# music-lights.net
KiCad netlist of a schematic drawn in EAGLE
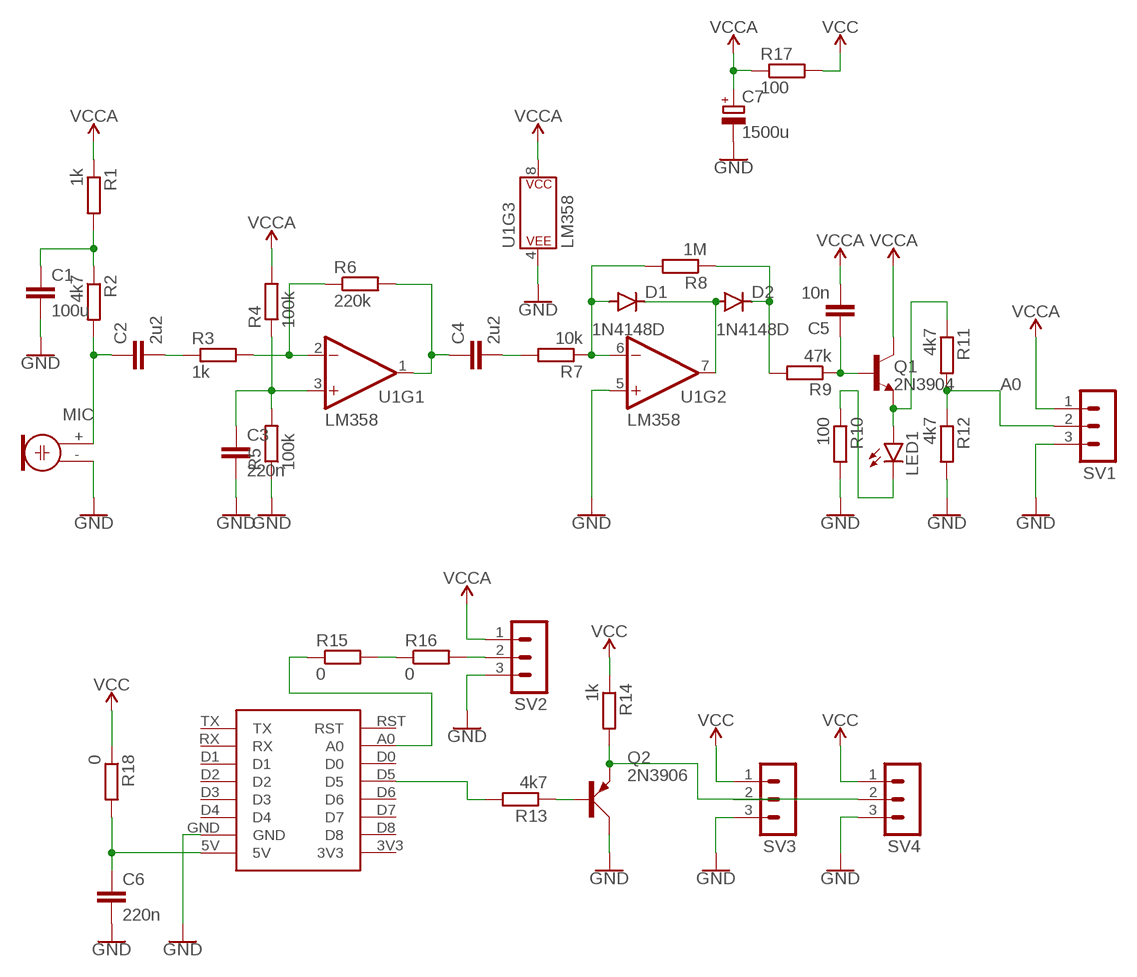
[diagram p0: schematic, sheet 1]

(export (version "E")
  (design (tool "Eeschema 10.0.6"))
  (components
    (comp (ref "C1")
      (value "100u")
      (footprint "eagle-import:C050-024X044")
      (libsource (lib "eagle-import") (part "C-EU050-024X044"))
    )
    (comp (ref "C2")
      (value "2u2")
      (footprint "eagle-import:C050-024X044")
      (libsource (lib "eagle-import") (part "C-EU050-024X044"))
    )
    (comp (ref "C3")
      (value "220n")
      (footprint "eagle-import:C050-024X044")
      (libsource (lib "eagle-import") (part "C-EU050-024X044"))
    )
    (comp (ref "C4")
      (value "2u2")
      (footprint "eagle-import:C050-024X044")
      (libsource (lib "eagle-import") (part "C-EU050-024X044"))
    )
    (comp (ref "C5")
      (value "10n")
      (footprint "eagle-import:C050-024X044")
      (libsource (lib "eagle-import") (part "C-EU050-024X044"))
    )
    (comp (ref "C6")
      (value "220n")
      (footprint "eagle-import:C050-024X044")
      (libsource (lib "eagle-import") (part "C-EU050-024X044"))
    )
    (comp (ref "C7")
      (value "1500u")
      (footprint "eagle-import:TT5D7L")
      (libsource (lib "eagle-import") (part "CPOL-EUTT5D7L"))
    )
    (comp (ref "D1")
      (value "1N4148D")
      (footprint "eagle-import:DO35-7")
      (libsource (lib "eagle-import") (part "1N4148DO35-7"))
    )
    (comp (ref "D2")
      (value "1N4148D")
      (footprint "eagle-import:DO35-7")
      (libsource (lib "eagle-import") (part "1N4148DO35-7"))
    )
    (comp (ref "LED1")
      (value "LED5MM")
      (footprint "eagle-import:LED5MM")
      (libsource (lib "eagle-import") (part "LED5MM"))
    )
    (comp (ref "MIC")
      (value "ELECTRET")
      (footprint "eagle-import:9.7ELECTRET")
      (libsource (lib "eagle-import") (part "ELECTRET"))
    )
    (comp (ref "Q1")
      (value "2N3904")
      (footprint "eagle-import:TO92")
      (libsource (lib "eagle-import") (part "2N3904"))
    )
    (comp (ref "Q2")
      (value "2N3906")
      (footprint "eagle-import:TO92D")
      (libsource (lib "eagle-import") (part "2N3906"))
    )
    (comp (ref "R1")
      (value "1k")
      (footprint "eagle-import:0207_7")
      (libsource (lib "eagle-import") (part "R-EU_0207/7"))
    )
    (comp (ref "R2")
      (value "4k7")
      (footprint "eagle-import:0207_7")
      (libsource (lib "eagle-import") (part "R-EU_0207/7"))
    )
    (comp (ref "R3")
      (value "1k")
      (footprint "eagle-import:0207_7")
      (libsource (lib "eagle-import") (part "R-EU_0207/7"))
    )
    (comp (ref "R4")
      (value "100k")
      (footprint "eagle-import:0207_7")
      (libsource (lib "eagle-import") (part "R-EU_0207/7"))
    )
    (comp (ref "R5")
      (value "100k")
      (footprint "eagle-import:0207_7")
      (libsource (lib "eagle-import") (part "R-EU_0207/7"))
    )
    (comp (ref "R6")
      (value "220k")
      (footprint "eagle-import:0207_7")
      (libsource (lib "eagle-import") (part "R-EU_0207/7"))
    )
    (comp (ref "R7")
      (value "10k")
      (footprint "eagle-import:0207_7")
      (libsource (lib "eagle-import") (part "R-EU_0207/7"))
    )
    (comp (ref "R8")
      (value "1M")
      (footprint "eagle-import:0207_7")
      (libsource (lib "eagle-import") (part "R-EU_0207/7"))
    )
    (comp (ref "R9")
      (value "47k")
      (footprint "eagle-import:0207_7")
      (libsource (lib "eagle-import") (part "R-EU_0207/7"))
    )
    (comp (ref "R10")
      (value "100")
      (footprint "eagle-import:0207_7")
      (libsource (lib "eagle-import") (part "R-EU_0207/7"))
    )
    (comp (ref "R11")
      (value "4k7")
      (footprint "eagle-import:0207_7")
      (libsource (lib "eagle-import") (part "R-EU_0207/7"))
    )
    (comp (ref "R12")
      (value "4k7")
      (footprint "eagle-import:0207_7")
      (libsource (lib "eagle-import") (part "R-EU_0207/7"))
    )
    (comp (ref "R13")
      (value "4k7")
      (footprint "eagle-import:0207_7")
      (libsource (lib "eagle-import") (part "R-EU_0207/7"))
    )
    (comp (ref "R14")
      (value "1k")
      (footprint "eagle-import:0207_7")
      (libsource (lib "eagle-import") (part "R-EU_0207/7"))
    )
    (comp (ref "R15")
      (value "0")
      (footprint "eagle-import:0207_7")
      (libsource (lib "eagle-import") (part "R-EU_0207/7"))
    )
    (comp (ref "R16")
      (value "0")
      (footprint "eagle-import:0207_7")
      (libsource (lib "eagle-import") (part "R-EU_0207/7"))
    )
    (comp (ref "R17")
      (value "100")
      (footprint "eagle-import:0207_7")
      (libsource (lib "eagle-import") (part "R-EU_0207/7"))
    )
    (comp (ref "R18")
      (value "0")
      (footprint "eagle-import:0207_7")
      (libsource (lib "eagle-import") (part "R-EU_0207/7"))
    )
    (comp (ref "SV1")
      (value "MA03-1")
      (footprint "eagle-import:MA03-1")
      (libsource (lib "eagle-import") (part "MA03-1"))
    )
    (comp (ref "SV2")
      (value "MA03-1")
      (footprint "eagle-import:MA03-1")
      (libsource (lib "eagle-import") (part "MA03-1"))
    )
    (comp (ref "SV3")
      (value "MA03-1")
      (footprint "eagle-import:MA03-1")
      (libsource (lib "eagle-import") (part "MA03-1"))
    )
    (comp (ref "SV4")
      (value "MA03-1")
      (footprint "eagle-import:MA03-1")
      (libsource (lib "eagle-import") (part "MA03-1"))
    )
    (comp (ref "U$1")
      (value "8266MINI")
      (footprint "eagle-import:8266MINI")
      (libsource (lib "eagle-import") (part "8266MINI"))
    )
    (comp (ref "U1")
      (value "LM358")
      (footprint "eagle-import:DIP08-KIT")
      (libsource (lib "eagle-import") (part "LM358KIT"))
    )
  )
  (nets
    (net (code "1") (name "/A0") (class "Default")
      (node (ref "R11") (pin "2") (pinfunction "2_2") (pintype "passive"))
      (node (ref "R12") (pin "1") (pinfunction "1_1") (pintype "passive"))
      (node (ref "SV1") (pin "2") (pinfunction "2_2") (pintype "passive"))
    )
    (net (code "2") (name "GND") (class "Default")
      (node (ref "C1") (pin "2") (pinfunction "2_2") (pintype "passive"))
      (node (ref "C3") (pin "2") (pinfunction "2_2") (pintype "passive"))
      (node (ref "C6") (pin "2") (pinfunction "2_2") (pintype "passive"))
      (node (ref "C7") (pin "-") (pinfunction "-_-") (pintype "passive"))
      (node (ref "MIC") (pin "-") (pinfunction "1_-") (pintype "passive"))
      (node (ref "Q2") (pin "C") (pinfunction "C_C") (pintype "passive"))
      (node (ref "R10") (pin "2") (pinfunction "2_2") (pintype "passive"))
      (node (ref "R12") (pin "2") (pinfunction "2_2") (pintype "passive"))
      (node (ref "R5") (pin "1") (pinfunction "1_1") (pintype "passive"))
      (node (ref "SV1") (pin "3") (pinfunction "3_3") (pintype "passive"))
      (node (ref "SV2") (pin "3") (pinfunction "3_3") (pintype "passive"))
      (node (ref "SV3") (pin "3") (pinfunction "3_3") (pintype "passive"))
      (node (ref "SV4") (pin "3") (pinfunction "3_3") (pintype "passive"))
      (node (ref "U$1") (pin "GND") (pinfunction "GND_GND") (pintype "bidirectional"))
      (node (ref "U1") (pin "4") (pinfunction "P$V-_4") (pintype "bidirectional"))
      (node (ref "U1") (pin "5") (pinfunction "+IN_5") (pintype "input"))
    )
    (net (code "3") (name "Net-(C1-Pad1)") (class "Default")
      (node (ref "C1") (pin "1") (pinfunction "1_1") (pintype "passive"))
      (node (ref "R1") (pin "2") (pinfunction "2_2") (pintype "passive"))
      (node (ref "R2") (pin "1") (pinfunction "1_1") (pintype "passive"))
    )
    (net (code "4") (name "Net-(C2-Pad2)") (class "Default")
      (node (ref "C2") (pin "2") (pinfunction "2_2") (pintype "passive"))
      (node (ref "R3") (pin "1") (pinfunction "1_1") (pintype "passive"))
    )
    (net (code "5") (name "Net-(C4-Pad2)") (class "Default")
      (node (ref "C4") (pin "2") (pinfunction "2_2") (pintype "passive"))
      (node (ref "R7") (pin "2") (pinfunction "2_2") (pintype "passive"))
    )
    (net (code "6") (name "Net-(C6-Pad1)") (class "Default")
      (node (ref "C6") (pin "1") (pinfunction "1_1") (pintype "passive"))
      (node (ref "R18") (pin "2") (pinfunction "2_2") (pintype "passive"))
      (node (ref "U$1") (pin "5V") (pinfunction "5V_5V") (pintype "bidirectional"))
    )
    (net (code "7") (name "Net-(D2-PadC)") (class "Default")
      (node (ref "D2") (pin "C") (pinfunction "C_C") (pintype "passive"))
      (node (ref "R8") (pin "1") (pinfunction "1_1") (pintype "passive"))
      (node (ref "R9") (pin "2") (pinfunction "2_2") (pintype "passive"))
    )
    (net (code "8") (name "Net-(LED1-C)") (class "Default")
      (node (ref "LED1") (pin "K") (pinfunction "C_K") (pintype "passive"))
      (node (ref "R10") (pin "1") (pinfunction "1_1") (pintype "passive"))
    )
    (net (code "9") (name "Net-(MIC-2)") (class "Default")
      (node (ref "C2") (pin "1") (pinfunction "1_1") (pintype "passive"))
      (node (ref "MIC") (pin "+") (pinfunction "2_+") (pintype "passive"))
      (node (ref "R2") (pin "2") (pinfunction "2_2") (pintype "passive"))
    )
    (net (code "10") (name "Net-(Q1-B)") (class "Default")
      (node (ref "C5") (pin "1") (pinfunction "1_1") (pintype "passive"))
      (node (ref "Q1") (pin "2") (pinfunction "B_2") (pintype "passive"))
      (node (ref "R9") (pin "1") (pinfunction "1_1") (pintype "passive"))
    )
    (net (code "11") (name "Net-(Q1-E)") (class "Default")
      (node (ref "LED1") (pin "A") (pinfunction "A_A") (pintype "passive"))
      (node (ref "Q1") (pin "3") (pinfunction "E_3") (pintype "passive"))
      (node (ref "R11") (pin "1") (pinfunction "1_1") (pintype "passive"))
    )
    (net (code "12") (name "Net-(Q2-PadB)") (class "Default")
      (node (ref "Q2") (pin "B") (pinfunction "B_B") (pintype "passive"))
      (node (ref "R13") (pin "1") (pinfunction "1_1") (pintype "passive"))
    )
    (net (code "13") (name "Net-(Q2-PadE)") (class "Default")
      (node (ref "Q2") (pin "E") (pinfunction "E_E") (pintype "passive"))
      (node (ref "R14") (pin "2") (pinfunction "2_2") (pintype "passive"))
      (node (ref "SV3") (pin "2") (pinfunction "2_2") (pintype "passive"))
      (node (ref "SV4") (pin "2") (pinfunction "2_2") (pintype "passive"))
    )
    (net (code "14") (name "Net-(R13-Pad2)") (class "Default")
      (node (ref "R13") (pin "2") (pinfunction "2_2") (pintype "passive"))
      (node (ref "U$1") (pin "D5") (pinfunction "D5_D5") (pintype "bidirectional"))
    )
    (net (code "15") (name "Net-(R15-Pad1)") (class "Default")
      (node (ref "R15") (pin "1") (pinfunction "1_1") (pintype "passive"))
      (node (ref "U$1") (pin "A0") (pinfunction "A0_A0") (pintype "bidirectional"))
    )
    (net (code "16") (name "Net-(R15-Pad2)") (class "Default")
      (node (ref "R15") (pin "2") (pinfunction "2_2") (pintype "passive"))
      (node (ref "R16") (pin "1") (pinfunction "1_1") (pintype "passive"))
    )
    (net (code "17") (name "Net-(R16-Pad2)") (class "Default")
      (node (ref "R16") (pin "2") (pinfunction "2_2") (pintype "passive"))
      (node (ref "SV2") (pin "2") (pinfunction "2_2") (pintype "passive"))
    )
    (net (code "18") (name "Net-(U1A-+IN)") (class "Default")
      (node (ref "C3") (pin "1") (pinfunction "1_1") (pintype "passive"))
      (node (ref "R4") (pin "1") (pinfunction "1_1") (pintype "passive"))
      (node (ref "R5") (pin "2") (pinfunction "2_2") (pintype "passive"))
      (node (ref "U1") (pin "3") (pinfunction "+IN_3") (pintype "input"))
    )
    (net (code "19") (name "Net-(U1A--IN)") (class "Default")
      (node (ref "R3") (pin "2") (pinfunction "2_2") (pintype "passive"))
      (node (ref "R6") (pin "1") (pinfunction "1_1") (pintype "passive"))
      (node (ref "U1") (pin "2") (pinfunction "-IN_2") (pintype "input"))
    )
    (net (code "20") (name "Net-(U1A-OUT)") (class "Default")
      (node (ref "C4") (pin "1") (pinfunction "1_1") (pintype "passive"))
      (node (ref "R6") (pin "2") (pinfunction "2_2") (pintype "passive"))
      (node (ref "U1") (pin "1") (pinfunction "OUT_1") (pintype "output"))
    )
    (net (code "21") (name "Net-(U1B--IN)") (class "Default")
      (node (ref "D1") (pin "A") (pinfunction "A_A") (pintype "passive"))
      (node (ref "R7") (pin "1") (pinfunction "1_1") (pintype "passive"))
      (node (ref "R8") (pin "2") (pinfunction "2_2") (pintype "passive"))
      (node (ref "U1") (pin "6") (pinfunction "-IN_6") (pintype "input"))
    )
    (net (code "22") (name "Net-(U1B-OUT)") (class "Default")
      (node (ref "D1") (pin "C") (pinfunction "C_C") (pintype "passive"))
      (node (ref "D2") (pin "A") (pinfunction "A_A") (pintype "passive"))
      (node (ref "U1") (pin "7") (pinfunction "OUT_7") (pintype "output"))
    )
    (net (code "23") (name "VCC") (class "Default")
      (node (ref "R14") (pin "1") (pinfunction "1_1") (pintype "passive"))
      (node (ref "R17") (pin "2") (pinfunction "2_2") (pintype "passive"))
      (node (ref "R18") (pin "1") (pinfunction "1_1") (pintype "passive"))
      (node (ref "SV3") (pin "1") (pinfunction "1_1") (pintype "passive"))
      (node (ref "SV4") (pin "1") (pinfunction "1_1") (pintype "passive"))
    )
    (net (code "24") (name "VCCA") (class "Default")
      (node (ref "C5") (pin "2") (pinfunction "2_2") (pintype "passive"))
      (node (ref "C7") (pin "+") (pinfunction "+_+") (pintype "passive"))
      (node (ref "Q1") (pin "1") (pinfunction "C_1") (pintype "passive"))
      (node (ref "R1") (pin "1") (pinfunction "1_1") (pintype "passive"))
      (node (ref "R17") (pin "1") (pinfunction "1_1") (pintype "passive"))
      (node (ref "R4") (pin "2") (pinfunction "2_2") (pintype "passive"))
      (node (ref "SV1") (pin "1") (pinfunction "1_1") (pintype "passive"))
      (node (ref "SV2") (pin "1") (pinfunction "1_1") (pintype "passive"))
      (node (ref "U1") (pin "8") (pinfunction "P$V+_8") (pintype "bidirectional"))
    )
    (net (code "25") (name "unconnected-(U$1-Pad3V3)") (class "Default")
      (node (ref "U$1") (pin "3V3") (pinfunction "3V3_3V3") (pintype "bidirectional"))
    )
    (net (code "26") (name "unconnected-(U$1-PadD0)") (class "Default")
      (node (ref "U$1") (pin "D0") (pinfunction "D0_D0") (pintype "bidirectional"))
    )
    (net (code "27") (name "unconnected-(U$1-PadD1)") (class "Default")
      (node (ref "U$1") (pin "D1") (pinfunction "D1_D1") (pintype "bidirectional"))
    )
    (net (code "28") (name "unconnected-(U$1-PadD2)") (class "Default")
      (node (ref "U$1") (pin "D2") (pinfunction "D2_D2") (pintype "bidirectional"))
    )
    (net (code "29") (name "unconnected-(U$1-PadD3)") (class "Default")
      (node (ref "U$1") (pin "D3") (pinfunction "D3_D3") (pintype "bidirectional"))
    )
    (net (code "30") (name "unconnected-(U$1-PadD4)") (class "Default")
      (node (ref "U$1") (pin "D4") (pinfunction "D4_D4") (pintype "bidirectional"))
    )
    (net (code "31") (name "unconnected-(U$1-PadD6)") (class "Default")
      (node (ref "U$1") (pin "D6") (pinfunction "D6_D6") (pintype "bidirectional"))
    )
    (net (code "32") (name "unconnected-(U$1-PadD7)") (class "Default")
      (node (ref "U$1") (pin "D7") (pinfunction "D7_D7") (pintype "bidirectional"))
    )
    (net (code "33") (name "unconnected-(U$1-PadD8)") (class "Default")
      (node (ref "U$1") (pin "D8") (pinfunction "D8_D8") (pintype "bidirectional"))
    )
    (net (code "34") (name "unconnected-(U$1-PadRST)") (class "Default")
      (node (ref "U$1") (pin "RST") (pinfunction "RST_RST") (pintype "bidirectional"))
    )
    (net (code "35") (name "unconnected-(U$1-PadRX)") (class "Default")
      (node (ref "U$1") (pin "RX") (pinfunction "RX_RX") (pintype "bidirectional"))
    )
    (net (code "36") (name "unconnected-(U$1-PadTX)") (class "Default")
      (node (ref "U$1") (pin "TX") (pinfunction "TX_TX") (pintype "bidirectional"))
    )
  )
)
